# kctlspi.net
KiCad netlist of a schematic drawn in EAGLE
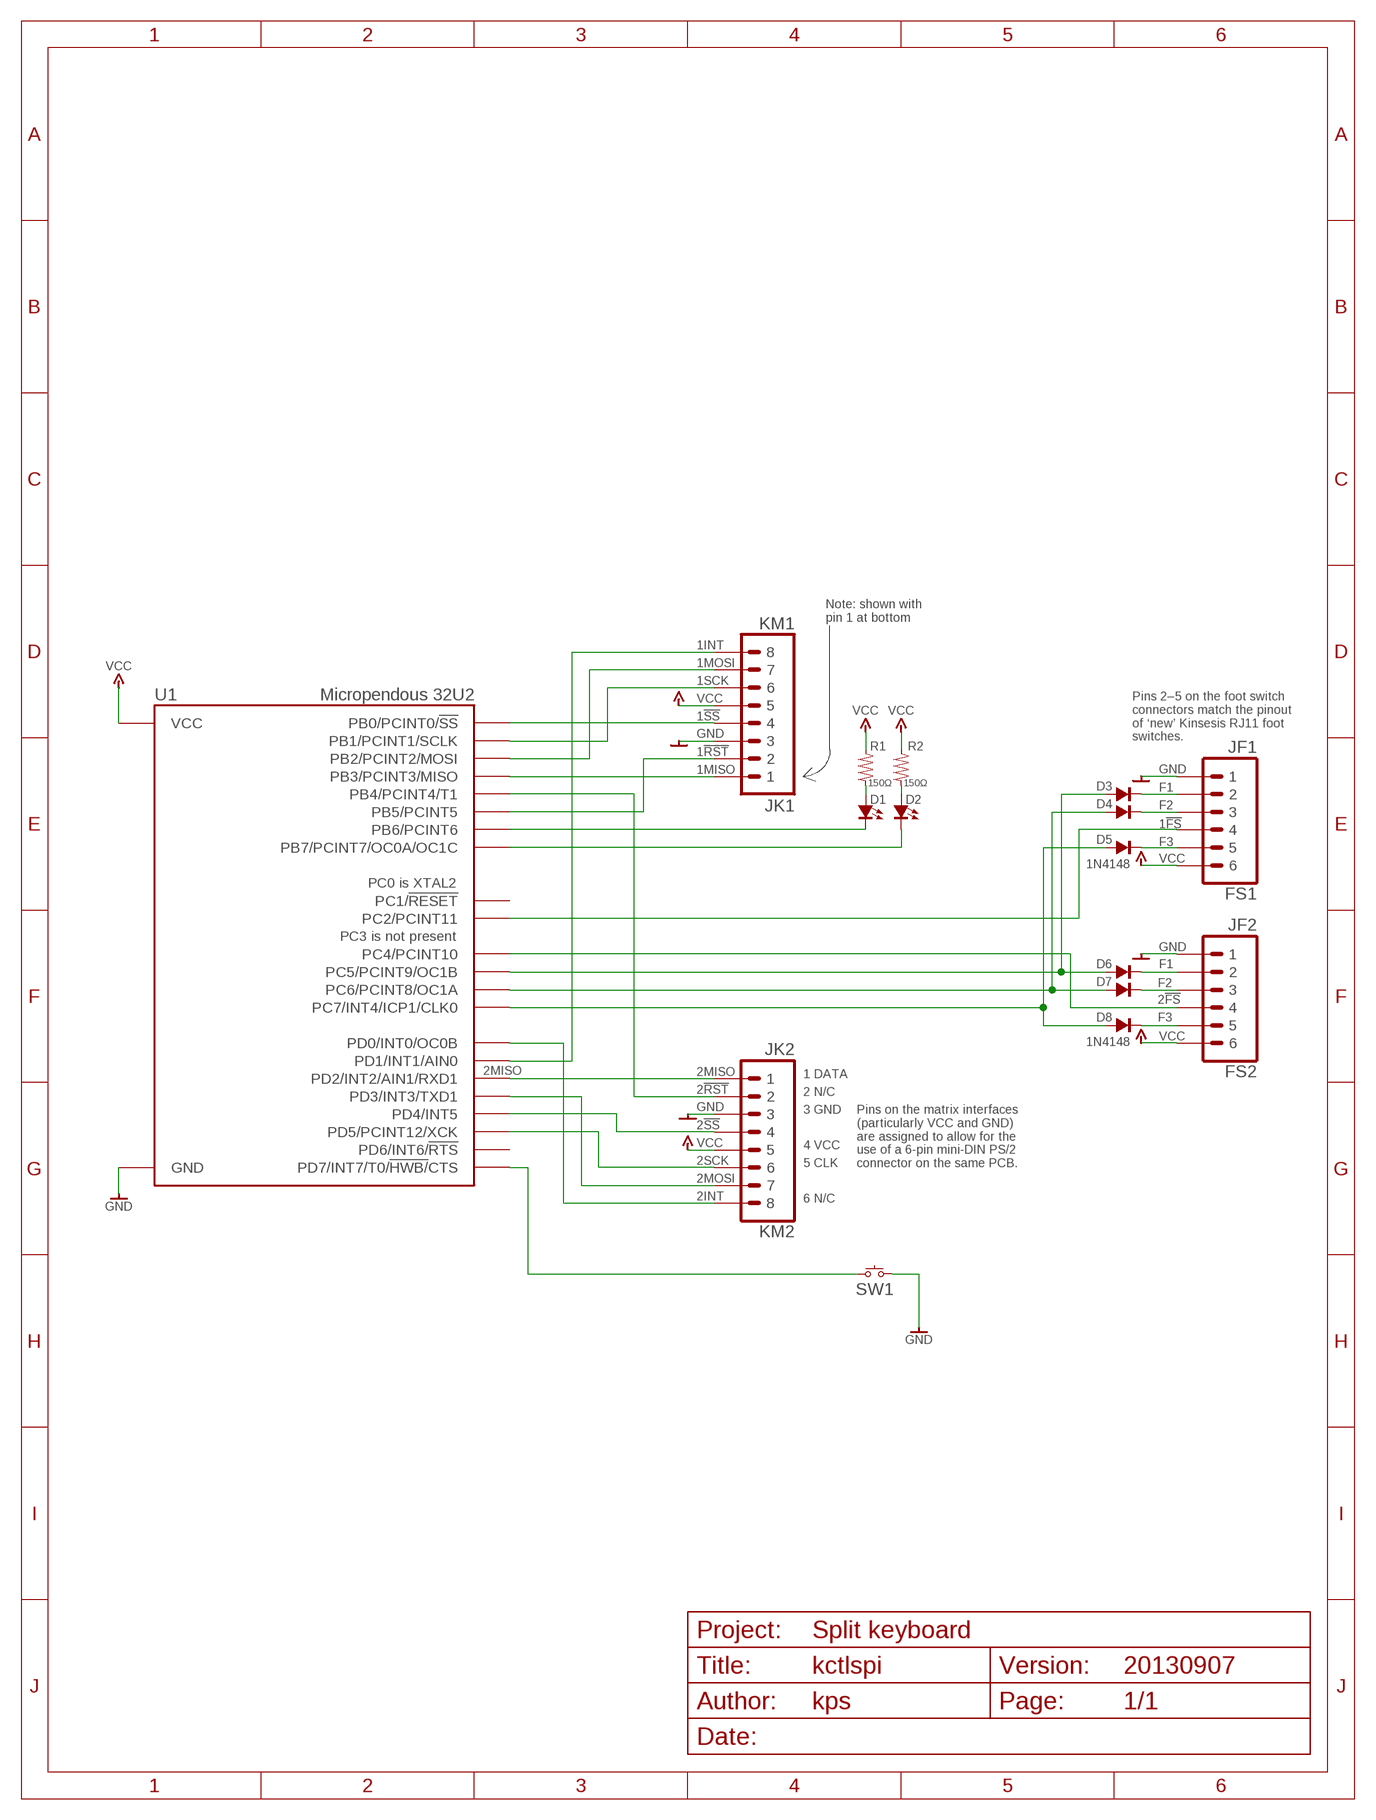
[diagram p0: schematic, sheet 1]

(export (version "E")
  (design (tool "Eeschema 10.0.6"))
  (components
    (comp (ref "D1")
      (value "LED")
      (footprint "eagle-import:2H-100-P-EXTSS")
      (libsource (lib "eagle-import") (part "LED"))
    )
    (comp (ref "D2")
      (value "LED")
      (footprint "eagle-import:2H-100-P-EXTSS")
      (libsource (lib "eagle-import") (part "LED"))
    )
    (comp (ref "D3")
      (value "1N4148")
      (footprint "eagle-import:2H-300-P-SMALLSS")
      (libsource (lib "eagle-import") (part "DIODE-300-SMALLSS"))
    )
    (comp (ref "D4")
      (value "1N4148")
      (footprint "eagle-import:2H-300-P-SMALLSS")
      (libsource (lib "eagle-import") (part "DIODE-300-SMALLSS"))
    )
    (comp (ref "D5")
      (value "1N4148")
      (footprint "eagle-import:2H-300-P-SMALLSS")
      (libsource (lib "eagle-import") (part "DIODE-300-SMALLSS"))
    )
    (comp (ref "D6")
      (value "1N4148")
      (footprint "eagle-import:2H-300-P-SMALLSS")
      (libsource (lib "eagle-import") (part "DIODE-300-SMALLSS"))
    )
    (comp (ref "D7")
      (value "1N4148")
      (footprint "eagle-import:2H-300-P-SMALLSS")
      (libsource (lib "eagle-import") (part "DIODE-300-SMALLSS"))
    )
    (comp (ref "D8")
      (value "1N4148")
      (footprint "eagle-import:2H-300-P-SMALLSS")
      (libsource (lib "eagle-import") (part "DIODE-300-SMALLSS"))
    )
    (comp (ref "JF1")
      (value "FS1")
      (footprint "eagle-import:J-8-RJ12-TE5555163")
      (libsource (lib "eagle-import") (part "J-6-RJ12-LP"))
    )
    (comp (ref "JF2")
      (value "FS2")
      (footprint "eagle-import:J-8-RJ12-TE5555163")
      (libsource (lib "eagle-import") (part "J-6-RJ12-LP"))
    )
    (comp (ref "JK1")
      (value "KM1")
      (footprint "eagle-import:J-8-MINIDIN-KMD11")
      (libsource (lib "eagle-import") (part "J-8-SHIELD-MINIDIN"))
    )
    (comp (ref "JK2")
      (value "KM2")
      (footprint "eagle-import:J-8-MINIDIN-KMD11")
      (libsource (lib "eagle-import") (part "J-8-SHIELD-MINIDIN"))
    )
    (comp (ref "R1")
      (value "150Ω")
      (footprint "eagle-import:2H-300-N-NOSS")
      (libsource (lib "eagle-import") (part "RESISTOR-300"))
    )
    (comp (ref "R2")
      (value "150Ω")
      (footprint "eagle-import:2H-300-N-NOSS")
      (libsource (lib "eagle-import") (part "RESISTOR-300"))
    )
    (comp (ref "SW1")
      (value "SW-TACTILE-RA")
      (footprint "eagle-import:SW-TACTILE-RA")
      (libsource (lib "eagle-import") (part "SW-TACTILE-RA"))
    )
    (comp (ref "U1")
      (value "Micropendous 32U2")
      (footprint "eagle-import:IC-ATMEGA32U2-NOOGROOVE")
      (libsource (lib "eagle-import") (part "IC-ATMEGA32U2-NOOGROOVE"))
    )
  )
  (nets
    (net (code "1") (name "/1INT") (class "Default")
      (node (ref "JK1") (pin "8") (pinfunction "8_8") (pintype "passive"))
      (node (ref "U1") (pin "PD1") (pinfunction "PD1/INT1/AIN0_PD1") (pintype "bidirectional"))
    )
    (net (code "2") (name "/1MISO") (class "Default")
      (node (ref "JK1") (pin "1") (pinfunction "1_1") (pintype "passive"))
      (node (ref "U1") (pin "PB3") (pinfunction "PB3/PCINT3/MISO_PB3") (pintype "bidirectional"))
    )
    (net (code "3") (name "/1MOSI") (class "Default")
      (node (ref "JK1") (pin "7") (pinfunction "7_7") (pintype "passive"))
      (node (ref "U1") (pin "PB2") (pinfunction "PB2/PCINT2/MOSI_PB2") (pintype "bidirectional"))
    )
    (net (code "4") (name "/1SCK") (class "Default")
      (node (ref "JK1") (pin "6") (pinfunction "6_6") (pintype "passive"))
      (node (ref "U1") (pin "PB1") (pinfunction "PB1/PCINT1/SCLK_PB1") (pintype "bidirectional"))
    )
    (net (code "5") (name "/1~{FS}") (class "Default")
      (node (ref "JF1") (pin "4") (pinfunction "4_4") (pintype "passive"))
      (node (ref "U1") (pin "PC2") (pinfunction "PC2/PCINT11_PC2") (pintype "bidirectional"))
    )
    (net (code "6") (name "/1~{RST}") (class "Default")
      (node (ref "JK1") (pin "2") (pinfunction "2_2") (pintype "passive"))
      (node (ref "U1") (pin "PB5") (pinfunction "PB5/PCINT5_PB5") (pintype "bidirectional"))
    )
    (net (code "7") (name "/1~{SS}") (class "Default")
      (node (ref "JK1") (pin "4") (pinfunction "4_4") (pintype "passive"))
      (node (ref "U1") (pin "PB0") (pinfunction "PB0/PCINT0/~{SS}_PB0") (pintype "bidirectional"))
    )
    (net (code "8") (name "/2INT") (class "Default")
      (node (ref "JK2") (pin "8") (pinfunction "8_8") (pintype "passive"))
      (node (ref "U1") (pin "PD0") (pinfunction "PD0/INT0/OC0B_PD0") (pintype "bidirectional"))
    )
    (net (code "9") (name "/2MISO") (class "Default")
      (node (ref "JK2") (pin "1") (pinfunction "1_1") (pintype "passive"))
      (node (ref "U1") (pin "PD2") (pinfunction "PD2/INT2/AIN1/RXD1_PD2") (pintype "bidirectional"))
    )
    (net (code "10") (name "/2MOSI") (class "Default")
      (node (ref "JK2") (pin "7") (pinfunction "7_7") (pintype "passive"))
      (node (ref "U1") (pin "PD3") (pinfunction "PD3/INT3/TXD1_PD3") (pintype "bidirectional"))
    )
    (net (code "11") (name "/2SCK") (class "Default")
      (node (ref "JK2") (pin "6") (pinfunction "6_6") (pintype "passive"))
      (node (ref "U1") (pin "PD5") (pinfunction "PD5/PCINT12/XCK_PD5") (pintype "bidirectional"))
    )
    (net (code "12") (name "/2~{FS}") (class "Default")
      (node (ref "JF2") (pin "4") (pinfunction "4_4") (pintype "passive"))
      (node (ref "U1") (pin "PC4") (pinfunction "PC4/PCINT10_PC4") (pintype "bidirectional"))
    )
    (net (code "13") (name "/2~{RST}") (class "Default")
      (node (ref "JK2") (pin "2") (pinfunction "2_2") (pintype "passive"))
      (node (ref "U1") (pin "PB4") (pinfunction "PB4/PCINT4/T1_PB4") (pintype "bidirectional"))
    )
    (net (code "14") (name "/2~{SS}") (class "Default")
      (node (ref "JK2") (pin "4") (pinfunction "4_4") (pintype "passive"))
      (node (ref "U1") (pin "PD4") (pinfunction "PD4/INT5_PD4") (pintype "bidirectional"))
    )
    (net (code "15") (name "/F1") (class "Default")
      (node (ref "D3") (pin "A") (pinfunction "A_A") (pintype "passive"))
      (node (ref "D6") (pin "A") (pinfunction "A_A") (pintype "passive"))
      (node (ref "U1") (pin "PC5") (pinfunction "PC5/PCINT9/OC1B_PC5") (pintype "bidirectional"))
    )
    (net (code "16") (name "/F2") (class "Default")
      (node (ref "D4") (pin "A") (pinfunction "A_A") (pintype "passive"))
      (node (ref "D7") (pin "A") (pinfunction "A_A") (pintype "passive"))
      (node (ref "U1") (pin "PC6") (pinfunction "PC6/PCINT8/OC1A_PC6") (pintype "bidirectional"))
    )
    (net (code "17") (name "/F3") (class "Default")
      (node (ref "D5") (pin "A") (pinfunction "A_A") (pintype "passive"))
      (node (ref "D8") (pin "A") (pinfunction "A_A") (pintype "passive"))
      (node (ref "U1") (pin "PC7") (pinfunction "PC7/INT4/ICP1/CLK0_PC7") (pintype "bidirectional"))
    )
    (net (code "18") (name "GND") (class "Default")
      (node (ref "JF1") (pin "1") (pinfunction "1_1") (pintype "passive"))
      (node (ref "JF2") (pin "1") (pinfunction "1_1") (pintype "passive"))
      (node (ref "JK1") (pin "3") (pinfunction "3_3") (pintype "passive"))
      (node (ref "JK2") (pin "3") (pinfunction "3_3") (pintype "passive"))
      (node (ref "SW1") (pin "2") (pinfunction "2_2") (pintype "passive"))
      (node (ref "U1") (pin "GND") (pinfunction "GND_GND") (pintype "power_in"))
    )
    (net (code "19") (name "Net-(D1-PadA)") (class "Default")
      (node (ref "D1") (pin "A") (pinfunction "A_A") (pintype "passive"))
      (node (ref "R1") (pin "1") (pinfunction "1_1") (pintype "passive"))
    )
    (net (code "20") (name "Net-(D2-PadA)") (class "Default")
      (node (ref "D2") (pin "A") (pinfunction "A_A") (pintype "passive"))
      (node (ref "R2") (pin "1") (pinfunction "1_1") (pintype "passive"))
    )
    (net (code "21") (name "Net-(D3-PadC)") (class "Default")
      (node (ref "D3") (pin "C") (pinfunction "C_C") (pintype "passive"))
      (node (ref "JF1") (pin "2") (pinfunction "2_2") (pintype "passive"))
    )
    (net (code "22") (name "Net-(D4-PadC)") (class "Default")
      (node (ref "D4") (pin "C") (pinfunction "C_C") (pintype "passive"))
      (node (ref "JF1") (pin "3") (pinfunction "3_3") (pintype "passive"))
    )
    (net (code "23") (name "Net-(D5-PadC)") (class "Default")
      (node (ref "D5") (pin "C") (pinfunction "C_C") (pintype "passive"))
      (node (ref "JF1") (pin "5") (pinfunction "5_5") (pintype "passive"))
    )
    (net (code "24") (name "Net-(D6-PadC)") (class "Default")
      (node (ref "D6") (pin "C") (pinfunction "C_C") (pintype "passive"))
      (node (ref "JF2") (pin "2") (pinfunction "2_2") (pintype "passive"))
    )
    (net (code "25") (name "Net-(D7-PadC)") (class "Default")
      (node (ref "D7") (pin "C") (pinfunction "C_C") (pintype "passive"))
      (node (ref "JF2") (pin "3") (pinfunction "3_3") (pintype "passive"))
    )
    (net (code "26") (name "Net-(D8-PadC)") (class "Default")
      (node (ref "D8") (pin "C") (pinfunction "C_C") (pintype "passive"))
      (node (ref "JF2") (pin "5") (pinfunction "5_5") (pintype "passive"))
    )
    (net (code "27") (name "Net-(U1-PB6{slash}PCINT6)") (class "Default")
      (node (ref "D1") (pin "C") (pinfunction "C_C") (pintype "passive"))
      (node (ref "U1") (pin "PB6") (pinfunction "PB6/PCINT6_PB6") (pintype "bidirectional"))
    )
    (net (code "28") (name "Net-(U1-PB7{slash}PCINT7{slash}OC0A{slash}OC1C)") (class "Default")
      (node (ref "D2") (pin "C") (pinfunction "C_C") (pintype "passive"))
      (node (ref "U1") (pin "PB7") (pinfunction "PB7/PCINT7/OC0A/OC1C_PB7") (pintype "bidirectional"))
    )
    (net (code "29") (name "Net-(U1-PD7{slash}INT7{slash}T0{slash}~{HWB{slash}}CTS)") (class "Default")
      (node (ref "SW1") (pin "1") (pinfunction "1_1") (pintype "passive"))
      (node (ref "U1") (pin "PD7") (pinfunction "PD7/INT7/T0/~{HWB/}CTS_PD7") (pintype "bidirectional"))
    )
    (net (code "30") (name "VCC") (class "Default")
      (node (ref "JF1") (pin "6") (pinfunction "6_6") (pintype "passive"))
      (node (ref "JF2") (pin "6") (pinfunction "6_6") (pintype "passive"))
      (node (ref "JK1") (pin "5") (pinfunction "5_5") (pintype "passive"))
      (node (ref "JK2") (pin "5") (pinfunction "5_5") (pintype "passive"))
      (node (ref "R1") (pin "2") (pinfunction "2_2") (pintype "passive"))
      (node (ref "R2") (pin "2") (pinfunction "2_2") (pintype "passive"))
      (node (ref "U1") (pin "+5V") (pinfunction "VCC_+5V") (pintype "power_in"))
    )
    (net (code "31") (name "unconnected-(U1-PC1{slash}~{RESET}-PadRESET)") (class "Default")
      (node (ref "U1") (pin "RESET") (pinfunction "PC1/~{RESET}_RESET") (pintype "bidirectional"))
    )
    (net (code "32") (name "unconnected-(U1-PD6{slash}INT6{slash}~{RTS}-PadPD6)") (class "Default")
      (node (ref "U1") (pin "PD6") (pinfunction "PD6/INT6/~{RTS}_PD6") (pintype "bidirectional"))
    )
  )
)
